# 5__Power_Supply.net
KiCad netlist of a schematic drawn in Altium Designer
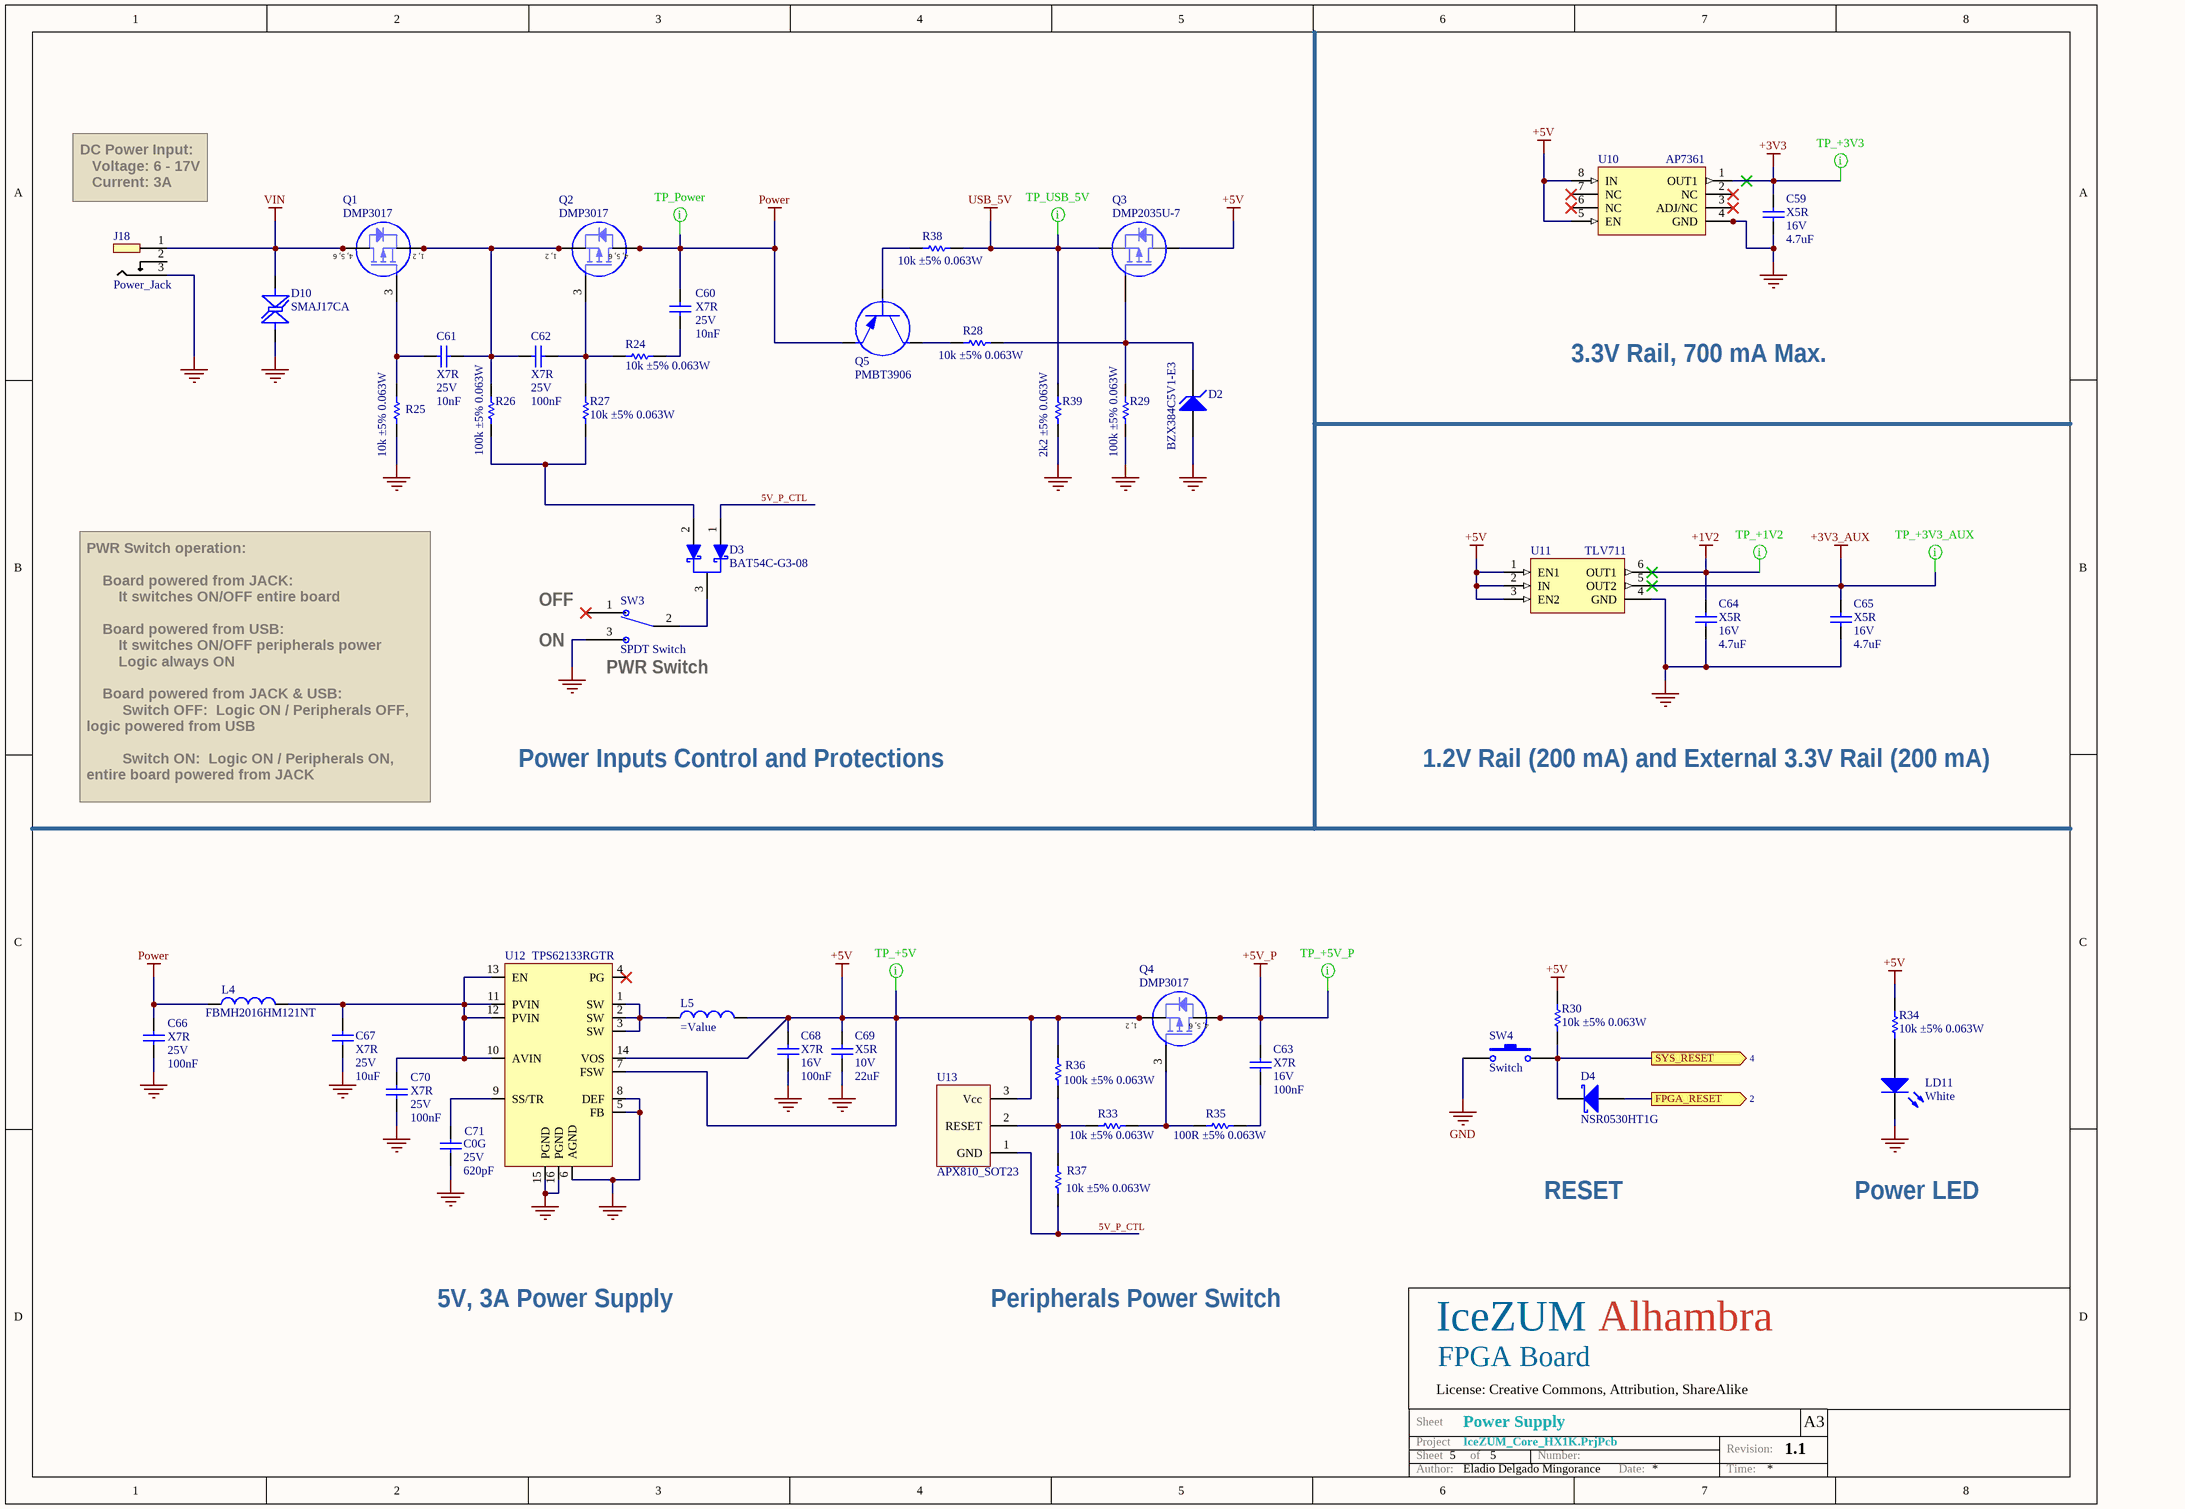
[diagram p0: [5]_Power_Supply.SchDoc]

(export (version "E")
  (design (tool "Eeschema 10.0.6"))
  (components
    (comp (ref "C59")
      (value "Capacitor")
      (footprint "C0603")
      (description "Capacitor SMD")
      (fields
        (field (name "DIELECTRIC") "X5R")
        (field (name "VOLTAGE") "16V")
        (field (name "CAPACITANCE") "4.7uF")
        (field (name "PART NUMBER") "C0603_4.7uF_16V_±10%")
        (field (name "TOLERANCE") "±10%")
      )
      (libsource (lib "") (part "Capacitor_1"))
    )
    (comp (ref "C60")
      (value "Capacitor")
      (footprint "C0603")
      (description "Capacitor SMD")
      (fields
        (field (name "DIELECTRIC") "X7R")
        (field (name "VOLTAGE") "25V")
        (field (name "CAPACITANCE") "10nF")
        (field (name "PART NUMBER") "C0603_10nF_25V_±10%")
        (field (name "TOLERANCE") "±10%")
      )
      (libsource (lib "Pasives_Capacitor_SMD") (part "Capacitor"))
    )
    (comp (ref "C61")
      (value "Capacitor")
      (footprint "C0603")
      (description "Capacitor SMD")
      (fields
        (field (name "DIELECTRIC") "X7R")
        (field (name "VOLTAGE") "25V")
        (field (name "CAPACITANCE") "10nF")
        (field (name "PART NUMBER") "C0603_10nF_25V_±10%")
        (field (name "TOLERANCE") "±10%")
      )
      (libsource (lib "Pasives_Capacitor_SMD") (part "Capacitor"))
    )
    (comp (ref "C62")
      (value "Capacitor")
      (footprint "C0603")
      (description "Capacitor SMD")
      (fields
        (field (name "DIELECTRIC") "X7R")
        (field (name "VOLTAGE") "25V")
        (field (name "CAPACITANCE") "100nF")
        (field (name "PART NUMBER") "C0603_100nF_25V_±10%")
        (field (name "TOLERANCE") "±10%")
      )
      (libsource (lib "") (part "Capacitor_1"))
    )
    (comp (ref "C63")
      (value "Capacitor")
      (footprint "C0402")
      (description "Capacitor SMD")
      (fields
        (field (name "DIELECTRIC") "X7R")
        (field (name "VOLTAGE") "16V")
        (field (name "CAPACITANCE") "100nF")
        (field (name "PART NUMBER") "C0402_100nF_16V_±10%")
        (field (name "TOLERANCE") "±10%")
      )
      (libsource (lib "") (part "Capacitor_1"))
    )
    (comp (ref "C64")
      (value "Capacitor")
      (footprint "C0603")
      (description "Capacitor SMD")
      (fields
        (field (name "DIELECTRIC") "X5R")
        (field (name "VOLTAGE") "16V")
        (field (name "CAPACITANCE") "4.7uF")
        (field (name "PART NUMBER") "C0603_4.7uF_16V_±10%")
        (field (name "TOLERANCE") "±10%")
      )
      (libsource (lib "") (part "Capacitor_1"))
    )
    (comp (ref "C65")
      (value "Capacitor")
      (footprint "C0603")
      (description "Capacitor SMD")
      (fields
        (field (name "DIELECTRIC") "X5R")
        (field (name "VOLTAGE") "16V")
        (field (name "CAPACITANCE") "4.7uF")
        (field (name "PART NUMBER") "C0603_4.7uF_16V_±10%")
        (field (name "TOLERANCE") "±10%")
      )
      (libsource (lib "") (part "Capacitor_1"))
    )
    (comp (ref "C66")
      (value "Capacitor")
      (footprint "C0603")
      (fields
        (field (name "DIELECTRIC") "X7R")
        (field (name "VOLTAGE") "25V")
        (field (name "CAPACITANCE") "100nF")
        (field (name "PART NUMBER") "C0603_100nF_25V_±10%")
        (field (name "TOLERANCE") "±10%")
        (field (name "MANUFACTURER") "Kemet")
      )
      (libsource (lib "") (part "Capacitor_1"))
    )
    (comp (ref "C67")
      (value "Capacitor")
      (footprint "C1206")
      (description "Capacitor SMD")
      (fields
        (field (name "DIELECTRIC") "X7R")
        (field (name "VOLTAGE") "25V")
        (field (name "CAPACITANCE") "10uF")
        (field (name "PART NUMBER") "C1206_10uF_25V_±10%")
        (field (name "TOLERANCE") "±10%")
      )
      (libsource (lib "") (part "Capacitor_1"))
    )
    (comp (ref "C68")
      (value "Capacitor")
      (footprint "C0402")
      (description "Capacitor SMD")
      (fields
        (field (name "DIELECTRIC") "X7R")
        (field (name "VOLTAGE") "16V")
        (field (name "CAPACITANCE") "100nF")
        (field (name "PART NUMBER") "C0402_100nF_16V_±10%")
        (field (name "TOLERANCE") "±10%")
      )
      (libsource (lib "") (part "Capacitor_1"))
    )
    (comp (ref "C69")
      (value "Capacitor")
      (footprint "C1206")
      (fields
        (field (name "DIELECTRIC") "X5R")
        (field (name "VOLTAGE") "10V")
        (field (name "CAPACITANCE") "22uF")
        (field (name "PART NUMBER") "C1206_22uF_10V_±20%")
        (field (name "TOLERANCE") "±20%")
        (field (name "MANUFACTURER") "Taiyo Yuden")
      )
      (libsource (lib "") (part "Capacitor_1"))
    )
    (comp (ref "C70")
      (value "Capacitor")
      (footprint "C0603")
      (fields
        (field (name "DIELECTRIC") "X7R")
        (field (name "VOLTAGE") "25V")
        (field (name "CAPACITANCE") "100nF")
        (field (name "PART NUMBER") "C0603_100nF_25V_±10%")
        (field (name "TOLERANCE") "±10%")
        (field (name "MANUFACTURER") "Kemet")
      )
      (libsource (lib "") (part "Capacitor_1"))
    )
    (comp (ref "C71")
      (value "Capacitor")
      (footprint "C0603")
      (fields
        (field (name "DIELECTRIC") "C0G")
        (field (name "VOLTAGE") "25V")
        (field (name "CAPACITANCE") "620pF")
        (field (name "PART NUMBER") "C0603_620pF_25V_±5%")
        (field (name "TOLERANCE") "±5%")
        (field (name "MANUFACTURER") "Murata")
      )
      (libsource (lib "") (part "Capacitor_1"))
    )
    (comp (ref "D2")
      (value "BZX384C5V1-E3")
      (footprint "SOD323")
      (description "Zener Diode")
      (fields (field (name "PART NUMBER") "BZX384C5V1") (field (name "TOLERANCE") "0,05"))
      (libsource (lib "Diodes") (part "Zener"))
    )
    (comp (ref "D3")
      (value "BAT54C-G3-08")
      (footprint "SOT23-3")
      (description "Dual Schottky Diode Common Cathode")
      (fields (field (name "PART NUMBER") "BAT54C") (field (name "MANUFACTURER") "Vishay"))
      (libsource (lib "Diodes") (part "Dual_Diode_Schottky_BAT54C"))
    )
    (comp (ref "D4")
      (value "NSR0530HT1G")
      (footprint "SOD323")
      (description "Schottky Diode")
      (fields (field (name "MANUFACTURER") "On Semiconductor"))
      (libsource (lib "Diodes") (part "Schottky"))
    )
    (comp (ref "D10")
      (value "SMAJ17CA")
      (footprint "DO-214AC-SMA_Bidir")
      (description "Protection, Bidirectional Transient Suppression Diodes")
      (fields (field (name "PART NUMBER") "TVS 17V Bi SMA") (field (name "VOLTAGE") "17V"))
      (libsource (lib "Protection") (part "Zener_Bidir_TVS"))
    )
    (comp (ref "J18")
      (value "Power_Jack")
      (footprint "Jack 2.1")
      (description "Connector, Power, DC Power Jack")
      (fields (field (name "PART NUMBER") "DC Power Jack") (field (name "MANUFACTURER") "Kycon"))
      (libsource (lib "Connectors_Power") (part "Power_Jack"))
    )
    (comp (ref "L4")
      (value "FBMH2016HM121NT")
      (footprint "L0806")
      (description "Ferrite Bead")
      (fields
        (field (name "PART NUMBER") "L0806_120R_0,015R_4,5A")
        (field (name "MANUFACTURER") "Taiyo Yuden")
      )
      (libsource (lib "Pasives_Inductor_SMD") (part "Ferrite Bead"))
    )
    (comp (ref "L5")
      (value "~")
      (footprint "L4040")
      (description "Inductor SMD")
      (fields (field (name "PART NUMBER") "2,2uH_4,7A") (field (name "MANUFACTURER") "Würth Elektronik"))
      (libsource (lib "Pasives_Inductor_SMD") (part "Inductor"))
    )
    (comp (ref "LD11")
      (value "White")
      (footprint "LED0603")
      (description "LED")
      (fields (field (name "PART NUMBER") "LW Q38G-Q2R3") (field (name "MANUFACTURER") "OSRAM Opto"))
      (libsource (lib "Optoelectronics") (part "LED"))
    )
    (comp (ref "Q1")
      (value "DMP3017")
      (footprint "U-DFN2523-6")
      (description "P-Channel MOSFET, 6 pin")
      (fields (field (name "MANUFACTURER") "Diodes Incorporated"))
      (libsource (lib "Transistors") (part "Mosfet_P DFN-6"))
    )
    (comp (ref "Q2")
      (value "DMP3017")
      (footprint "U-DFN2523-6")
      (description "P-Channel MOSFET, 6 pin")
      (fields (field (name "MANUFACTURER") "Diodes Incorporated"))
      (libsource (lib "Transistors") (part "Mosfet_P DFN-6"))
    )
    (comp (ref "Q3")
      (value "DMP2035U-7")
      (footprint "SOT23-3")
      (description "PFET")
      (fields (field (name "PART NUMBER") "DMP2035U") (field (name "MANUFACTURER") "Diodes Incorporated"))
      (libsource (lib "Semiconductors_Transistors") (part "Mosfet_P"))
    )
    (comp (ref "Q4")
      (value "DMP3017")
      (footprint "U-DFN2523-6")
      (description "P-Channel MOSFET, 6 pin")
      (fields (field (name "MANUFACTURER") "Diodes Incorporated"))
      (libsource (lib "Transistors") (part "Mosfet_P DFN-6"))
    )
    (comp (ref "Q5")
      (value "PMBT3906")
      (footprint "SOT23-3")
      (description "PNP")
      (fields (field (name "MANUFACTURER") "NXP"))
      (libsource (lib "Semiconductors_Transistors") (part "PNP"))
    )
    (comp (ref "R24")
      (value "10k ±5% 0.063W")
      (footprint "R0402")
      (description "Resistor, SMD")
      (fields (field (name "TOLERANCE") "±5%") (field (name "POWER") "0.063W"))
      (libsource (lib "Pasives_Resistor_SMD") (part "Resistor"))
    )
    (comp (ref "R25")
      (value "10k ±5% 0.063W")
      (footprint "R0402")
      (description "Resistor, SMD")
      (fields (field (name "TOLERANCE") "±5%") (field (name "POWER") "0.063W"))
      (libsource (lib "Pasives_Resistor_SMD") (part "Resistor"))
    )
    (comp (ref "R26")
      (value "100k ±5% 0.063W")
      (footprint "R0402")
      (description "Resistor, SMD")
      (fields (field (name "TOLERANCE") "±5%") (field (name "POWER") "0.063W"))
      (libsource (lib "Pasives_Resistor_SMD") (part "Resistor"))
    )
    (comp (ref "R27")
      (value "10k ±5% 0.063W")
      (footprint "R0402")
      (description "Resistor, SMD")
      (fields (field (name "TOLERANCE") "±5%") (field (name "POWER") "0.063W"))
      (libsource (lib "Pasives_Resistor_SMD") (part "Resistor"))
    )
    (comp (ref "R28")
      (value "10k ±5% 0.063W")
      (footprint "R0402")
      (description "Resistor, SMD")
      (fields (field (name "TOLERANCE") "±5%") (field (name "POWER") "0.063W"))
      (libsource (lib "Pasives_Resistor_SMD") (part "Resistor"))
    )
    (comp (ref "R29")
      (value "100k ±5% 0.063W")
      (footprint "R0402")
      (description "Resistor, SMD")
      (fields (field (name "TOLERANCE") "±5%") (field (name "POWER") "0.063W"))
      (libsource (lib "Pasives_Resistor_SMD") (part "Resistor"))
    )
    (comp (ref "R30")
      (value "10k ±5% 0.063W")
      (footprint "R0402")
      (description "Resistor, SMD")
      (fields (field (name "TOLERANCE") "±5%") (field (name "POWER") "0.063W"))
      (libsource (lib "Pasives_Resistor_SMD") (part "Resistor"))
    )
    (comp (ref "R33")
      (value "10k ±5% 0.063W")
      (footprint "R0402")
      (description "Resistor, SMD")
      (fields (field (name "TOLERANCE") "±5%") (field (name "POWER") "0.063W"))
      (libsource (lib "Pasives_Resistor_SMD") (part "Resistor"))
    )
    (comp (ref "R34")
      (value "10k ±5% 0.063W")
      (footprint "R0402")
      (description "Resistor, SMD")
      (fields (field (name "TOLERANCE") "±5%") (field (name "POWER") "0.063W"))
      (libsource (lib "Pasives_Resistor_SMD") (part "Resistor"))
    )
    (comp (ref "R35")
      (value "100R ±5% 0.063W")
      (footprint "R0402")
      (description "Resistor, SMD")
      (fields (field (name "TOLERANCE") "±5%") (field (name "POWER") "0.063W"))
      (libsource (lib "Pasives_Resistor_SMD") (part "Resistor"))
    )
    (comp (ref "R36")
      (value "100k ±5% 0.063W")
      (footprint "R0402")
      (description "Resistor, SMD")
      (fields (field (name "TOLERANCE") "±5%") (field (name "POWER") "0.063W"))
      (libsource (lib "Pasives_Resistor_SMD") (part "Resistor"))
    )
    (comp (ref "R37")
      (value "10k ±5% 0.063W")
      (footprint "R0402")
      (description "Resistor, SMD")
      (fields (field (name "TOLERANCE") "±5%") (field (name "POWER") "0.063W"))
      (libsource (lib "Pasives_Resistor_SMD") (part "Resistor"))
    )
    (comp (ref "R38")
      (value "10k ±5% 0.063W")
      (footprint "R0402")
      (description "Resistor, SMD")
      (fields (field (name "TOLERANCE") "±5%") (field (name "POWER") "0.063W"))
      (libsource (lib "Pasives_Resistor_SMD") (part "Resistor"))
    )
    (comp (ref "R39")
      (value "2k2 ±5% 0.063W")
      (footprint "R0402")
      (description "Resistor, SMD")
      (fields (field (name "TOLERANCE") "±5%") (field (name "POWER") "0.063W"))
      (libsource (lib "Pasives_Resistor_SMD") (part "Resistor"))
    )
    (comp (ref "SW3")
      (value "SPDT Switch")
      (footprint "Slide SW SPDT Right Angle")
      (fields (field (name "PART NUMBER") "Switch SPDT") (field (name "MANUFACTURER") "Würth Elektronik"))
      (libsource (lib "Electromechanical") (part "SPDT Switch"))
    )
    (comp (ref "SW4")
      (value "Switch")
      (footprint "SW_Vert_THT_7.5x6x6.5")
      (description "Micro miniature pushbutton surface Switch")
      (fields (field (name "PART NUMBER") "SW Vertical THT") (field (name "MANUFACTURER") "C&K Components"))
      (libsource (lib "Electromechanical") (part "Switch"))
    )
    (comp (ref "U10")
      (value "AP7361")
      (footprint "U-DFN3030-8")
      (description "LDO Regulator, 8 pin, adjustable and fixed mode with enable")
      (fields (field (name "MANUFACTURER") "Diodes Inc."))
      (libsource (lib "Power_Regulator") (part "AP7361_DFN"))
    )
    (comp (ref "U11")
      (value "TLV711")
      (footprint "WSON-6-1,5x1,5mm")
      (description "LDO Regulator, Dual, 6 pin")
      (fields (field (name "MANUFACTURER") "Texas Instruments"))
      (libsource (lib "Power_Regulator") (part "TLV71x"))
    )
    (comp (ref "U12")
      (value "TPS62133RGTR")
      (footprint "QFN16")
      (description "3A High Efficient Synchronous Step Down Converter with DCS™ Control")
      (fields (field (name "PART NUMBER") "TPS62133") (field (name "MANUFACTURER") "Texas Instruments"))
      (libsource (lib "Power_Regulator") (part "TPS6213x"))
    )
    (comp (ref "U13")
      (value "APX810_SOT23")
      (footprint "SOT23-3")
      (description "Voltage supervisor, Reset active high, 200ms")
      (fields (field (name "PART NUMBER") "APX810") (field (name "MANUFACTURER") "Diodes Incorporated"))
      (libsource (lib "Power_Supervisor") (part "APX810_SOT23"))
    )
  )
  (nets
    (net (code "1") (name "+1V2") (class "Default")
      (node (ref "C64") (pin "2") (pinfunction "2_2") (pintype "passive"))
      (node (ref "U11") (pin "6") (pinfunction "OUT1_6") (pintype "output"))
    )
    (net (code "2") (name "+3V3") (class "Default")
      (node (ref "C59") (pin "2") (pinfunction "2_2") (pintype "passive"))
      (node (ref "U10") (pin "1") (pinfunction "OUT1_1") (pintype "output"))
    )
    (net (code "3") (name "+3V3_AUX") (class "Default")
      (node (ref "C65") (pin "2") (pinfunction "2_2") (pintype "passive"))
      (node (ref "U11") (pin "5") (pinfunction "OUT2_5") (pintype "output"))
    )
    (net (code "4") (name "+5V") (class "Default")
      (node (ref "C68") (pin "2") (pinfunction "2_2") (pintype "passive"))
      (node (ref "C69") (pin "2") (pinfunction "2_2") (pintype "passive"))
      (node (ref "L5") (pin "2") (pinfunction "2_2") (pintype "passive"))
      (node (ref "Q3") (pin "3") (pinfunction "D_3") (pintype "passive"))
      (node (ref "Q4") (pin "1") (pinfunction "S_1") (pintype "passive"))
      (node (ref "Q4") (pin "2") (pinfunction "S_2") (pintype "passive"))
      (node (ref "R30") (pin "2") (pinfunction "2_2") (pintype "passive"))
      (node (ref "R34") (pin "2") (pinfunction "2_2") (pintype "passive"))
      (node (ref "R36") (pin "1") (pinfunction "1_1") (pintype "passive"))
      (node (ref "U10") (pin "5") (pinfunction "EN_5") (pintype "input"))
      (node (ref "U10") (pin "8") (pinfunction "IN_8") (pintype "input"))
      (node (ref "U11") (pin "1") (pinfunction "EN1_1") (pintype "input"))
      (node (ref "U11") (pin "2") (pinfunction "IN_2") (pintype "input"))
      (node (ref "U11") (pin "3") (pinfunction "EN2_3") (pintype "input"))
      (node (ref "U12") (pin "14") (pinfunction "VOS_14") (pintype "passive"))
      (node (ref "U12") (pin "7") (pinfunction "FSW_7") (pintype "passive"))
      (node (ref "U13") (pin "3") (pinfunction "Vcc_3") (pintype "passive"))
    )
    (net (code "5") (name "+5V_P") (class "Default")
      (node (ref "C63") (pin "2") (pinfunction "2_2") (pintype "passive"))
      (node (ref "Q4") (pin "4") (pinfunction "D_4") (pintype "passive"))
      (node (ref "Q4") (pin "5") (pinfunction "D_5") (pintype "passive"))
      (node (ref "Q4") (pin "6") (pinfunction "D_6") (pintype "passive"))
    )
    (net (code "6") (name "/5V_P_CTL") (class "Default")
      (node (ref "D3") (pin "1") (pinfunction "A1_1") (pintype "passive"))
      (node (ref "R37") (pin "2") (pinfunction "2_2") (pintype "passive"))
      (node (ref "U13") (pin "1") (pinfunction "GND_1") (pintype "passive"))
    )
    (net (code "7") (name "/FPGA_RESET") (class "Default")
      (node (ref "D4") (pin "A") (pinfunction "A_A") (pintype "passive"))
    )
    (net (code "8") (name "/SYS_RESET") (class "Default")
      (node (ref "D4") (pin "k") (pinfunction "K_k") (pintype "passive"))
      (node (ref "R30") (pin "1") (pinfunction "1_1") (pintype "passive"))
      (node (ref "SW4") (pin "1") (pinfunction "1_1") (pintype "passive"))
    )
    (net (code "9") (name "GND") (class "Default")
      (node (ref "C59") (pin "1") (pinfunction "1_1") (pintype "passive"))
      (node (ref "C64") (pin "1") (pinfunction "1_1") (pintype "passive"))
      (node (ref "C65") (pin "1") (pinfunction "1_1") (pintype "passive"))
      (node (ref "C66") (pin "1") (pinfunction "1_1") (pintype "passive"))
      (node (ref "C67") (pin "1") (pinfunction "1_1") (pintype "passive"))
      (node (ref "C68") (pin "1") (pinfunction "1_1") (pintype "passive"))
      (node (ref "C69") (pin "1") (pinfunction "1_1") (pintype "passive"))
      (node (ref "C70") (pin "1") (pinfunction "1_1") (pintype "passive"))
      (node (ref "C71") (pin "1") (pinfunction "1_1") (pintype "passive"))
      (node (ref "D10") (pin "A") (pinfunction "A_A") (pintype "passive"))
      (node (ref "D2") (pin "A") (pinfunction "A_A") (pintype "passive"))
      (node (ref "J18") (pin "3") (pinfunction "3_3") (pintype "passive"))
      (node (ref "LD11") (pin "K") (pinfunction "K_K") (pintype "passive"))
      (node (ref "R25") (pin "2") (pinfunction "2_2") (pintype "passive"))
      (node (ref "R29") (pin "1") (pinfunction "1_1") (pintype "passive"))
      (node (ref "R39") (pin "1") (pinfunction "1_1") (pintype "passive"))
      (node (ref "SW3") (pin "3") (pinfunction "3_3") (pintype "passive"))
      (node (ref "SW4") (pin "2") (pinfunction "2_2") (pintype "passive"))
      (node (ref "U10") (pin "0") (pinfunction "TP_0") (pintype "power_in"))
      (node (ref "U10") (pin "4") (pinfunction "GND_4") (pintype "power_in"))
      (node (ref "U11") (pin "4") (pinfunction "GND_4") (pintype "power_in"))
      (node (ref "U12") (pin "15") (pinfunction "PGND_15") (pintype "passive"))
      (node (ref "U12") (pin "16") (pinfunction "PGND_16") (pintype "passive"))
      (node (ref "U12") (pin "5") (pinfunction "FB_5") (pintype "passive"))
      (node (ref "U12") (pin "6") (pinfunction "AGND_6") (pintype "passive"))
      (node (ref "U12") (pin "8") (pinfunction "DEF_8") (pintype "passive"))
    )
    (net (code "10") (name "Net-(C60-Pad1)") (class "Default")
      (node (ref "C60") (pin "1") (pinfunction "1_1") (pintype "passive"))
      (node (ref "R24") (pin "2") (pinfunction "2_2") (pintype "passive"))
    )
    (net (code "11") (name "Net-(C61-Pad1)") (class "Default")
      (node (ref "C61") (pin "1") (pinfunction "1_1") (pintype "passive"))
      (node (ref "C62") (pin "2") (pinfunction "2_2") (pintype "passive"))
      (node (ref "Q1") (pin "1") (pinfunction "S_1") (pintype "passive"))
      (node (ref "Q1") (pin "2") (pinfunction "S_2") (pintype "passive"))
      (node (ref "Q2") (pin "1") (pinfunction "S_1") (pintype "passive"))
      (node (ref "Q2") (pin "2") (pinfunction "S_2") (pintype "passive"))
      (node (ref "R26") (pin "1") (pinfunction "1_1") (pintype "passive"))
    )
    (net (code "12") (name "Net-(C63-Pad1)") (class "Default")
      (node (ref "C63") (pin "1") (pinfunction "1_1") (pintype "passive"))
      (node (ref "R35") (pin "2") (pinfunction "2_2") (pintype "passive"))
    )
    (net (code "13") (name "Net-(D2-K)") (class "Default")
      (node (ref "D2") (pin "k") (pinfunction "K_k") (pintype "passive"))
      (node (ref "Q3") (pin "1") (pinfunction "G_1") (pintype "passive"))
      (node (ref "R28") (pin "2") (pinfunction "2_2") (pintype "passive"))
      (node (ref "R29") (pin "2") (pinfunction "2_2") (pintype "passive"))
    )
    (net (code "14") (name "Net-(D3-A2)") (class "Default")
      (node (ref "D3") (pin "2") (pinfunction "A2_2") (pintype "passive"))
      (node (ref "R26") (pin "2") (pinfunction "2_2") (pintype "passive"))
      (node (ref "R27") (pin "2") (pinfunction "2_2") (pintype "passive"))
    )
    (net (code "15") (name "Net-(D3-K)") (class "Default")
      (node (ref "D3") (pin "3") (pinfunction "K_3") (pintype "passive"))
      (node (ref "SW3") (pin "2") (pinfunction "2_2") (pintype "passive"))
    )
    (net (code "16") (name "Net-(L5-Pad1)") (class "Default")
      (node (ref "L5") (pin "1") (pinfunction "1_1") (pintype "passive"))
      (node (ref "U12") (pin "1") (pinfunction "SW_1") (pintype "passive"))
      (node (ref "U12") (pin "2") (pinfunction "SW_2") (pintype "passive"))
      (node (ref "U12") (pin "3") (pinfunction "SW_3") (pintype "passive"))
    )
    (net (code "17") (name "Net-(LD11-PadA)") (class "Default")
      (node (ref "LD11") (pin "A") (pinfunction "A_A") (pintype "passive"))
      (node (ref "R34") (pin "1") (pinfunction "1_1") (pintype "passive"))
    )
    (net (code "18") (name "Net-(Q1-G)") (class "Default")
      (node (ref "C61") (pin "2") (pinfunction "2_2") (pintype "passive"))
      (node (ref "Q1") (pin "3") (pinfunction "G_3") (pintype "passive"))
      (node (ref "R25") (pin "1") (pinfunction "1_1") (pintype "passive"))
    )
    (net (code "19") (name "Net-(Q2-G)") (class "Default")
      (node (ref "C62") (pin "1") (pinfunction "1_1") (pintype "passive"))
      (node (ref "Q2") (pin "3") (pinfunction "G_3") (pintype "passive"))
      (node (ref "R24") (pin "1") (pinfunction "1_1") (pintype "passive"))
      (node (ref "R27") (pin "1") (pinfunction "1_1") (pintype "passive"))
    )
    (net (code "20") (name "Net-(Q4-G)") (class "Default")
      (node (ref "Q4") (pin "3") (pinfunction "G_3") (pintype "passive"))
      (node (ref "R33") (pin "2") (pinfunction "2_2") (pintype "passive"))
      (node (ref "R35") (pin "1") (pinfunction "1_1") (pintype "passive"))
    )
    (net (code "21") (name "Net-(Q5-B)") (class "Default")
      (node (ref "Q5") (pin "1") (pinfunction "B_1") (pintype "passive"))
      (node (ref "R38") (pin "1") (pinfunction "1_1") (pintype "passive"))
    )
    (net (code "22") (name "Net-(Q5-C)") (class "Default")
      (node (ref "Q5") (pin "3") (pinfunction "C_3") (pintype "passive"))
      (node (ref "R28") (pin "1") (pinfunction "1_1") (pintype "passive"))
    )
    (net (code "23") (name "Net-(U12-AVIN)") (class "Default")
      (node (ref "C67") (pin "2") (pinfunction "2_2") (pintype "passive"))
      (node (ref "C70") (pin "2") (pinfunction "2_2") (pintype "passive"))
      (node (ref "L4") (pin "2") (pinfunction "2_2") (pintype "passive"))
      (node (ref "U12") (pin "10") (pinfunction "AVIN_10") (pintype "passive"))
      (node (ref "U12") (pin "11") (pinfunction "PVIN_11") (pintype "passive"))
      (node (ref "U12") (pin "12") (pinfunction "PVIN_12") (pintype "passive"))
      (node (ref "U12") (pin "13") (pinfunction "EN_13") (pintype "passive"))
    )
    (net (code "24") (name "Net-(U12-SS{slash}TR)") (class "Default")
      (node (ref "C71") (pin "2") (pinfunction "2_2") (pintype "passive"))
      (node (ref "U12") (pin "9") (pinfunction "SS/TR_9") (pintype "passive"))
    )
    (net (code "25") (name "Net-(U13-RESET)") (class "Default")
      (node (ref "R33") (pin "1") (pinfunction "1_1") (pintype "passive"))
      (node (ref "R36") (pin "2") (pinfunction "2_2") (pintype "passive"))
      (node (ref "R37") (pin "1") (pinfunction "1_1") (pintype "passive"))
      (node (ref "U13") (pin "2") (pinfunction "RESET_2") (pintype "passive"))
    )
    (net (code "26") (name "Power") (class "Default")
      (node (ref "C60") (pin "2") (pinfunction "2_2") (pintype "passive"))
      (node (ref "C66") (pin "2") (pinfunction "2_2") (pintype "passive"))
      (node (ref "L4") (pin "1") (pinfunction "1_1") (pintype "passive"))
      (node (ref "Q2") (pin "4") (pinfunction "D_4") (pintype "passive"))
      (node (ref "Q2") (pin "5") (pinfunction "D_5") (pintype "passive"))
      (node (ref "Q2") (pin "6") (pinfunction "D_6") (pintype "passive"))
      (node (ref "Q5") (pin "2") (pinfunction "E_2") (pintype "passive"))
    )
    (net (code "27") (name "USB_5V") (class "Default")
      (node (ref "Q3") (pin "2") (pinfunction "S_2") (pintype "passive"))
      (node (ref "R38") (pin "2") (pinfunction "2_2") (pintype "passive"))
      (node (ref "R39") (pin "2") (pinfunction "2_2") (pintype "passive"))
    )
    (net (code "28") (name "VIN") (class "Default")
      (node (ref "D10") (pin "K") (pinfunction "K_K") (pintype "passive"))
      (node (ref "J18") (pin "1") (pinfunction "1_1") (pintype "passive"))
      (node (ref "Q1") (pin "4") (pinfunction "D_4") (pintype "passive"))
      (node (ref "Q1") (pin "5") (pinfunction "D_5") (pintype "passive"))
      (node (ref "Q1") (pin "6") (pinfunction "D_6") (pintype "passive"))
    )
    (net (code "29") (name "unconnected-(J18-Pad2)") (class "Default")
      (node (ref "J18") (pin "2") (pinfunction "2_2") (pintype "passive"))
    )
    (net (code "30") (name "unconnected-(SW3-Pad1)") (class "Default")
      (node (ref "SW3") (pin "1") (pinfunction "1_1") (pintype "passive+no_connect"))
    )
    (net (code "31") (name "unconnected-(U10-ADJ{slash}NC-Pad3)") (class "Default")
      (node (ref "U10") (pin "3") (pinfunction "ADJ/NC_3") (pintype "passive+no_connect"))
    )
    (net (code "32") (name "unconnected-(U10-NC-Pad2)") (class "Default")
      (node (ref "U10") (pin "2") (pinfunction "NC_2") (pintype "passive+no_connect"))
    )
    (net (code "33") (name "unconnected-(U10-NC-Pad6)") (class "Default")
      (node (ref "U10") (pin "6") (pinfunction "NC_6") (pintype "passive+no_connect"))
    )
    (net (code "34") (name "unconnected-(U10-NC-Pad7)") (class "Default")
      (node (ref "U10") (pin "7") (pinfunction "NC_7") (pintype "passive+no_connect"))
    )
    (net (code "35") (name "unconnected-(U12-PG-Pad4)") (class "Default")
      (node (ref "U12") (pin "4") (pinfunction "PG_4") (pintype "passive+no_connect"))
    )
  )
)
